# MAX31865.net
KiCad netlist of a schematic drawn in EAGLE
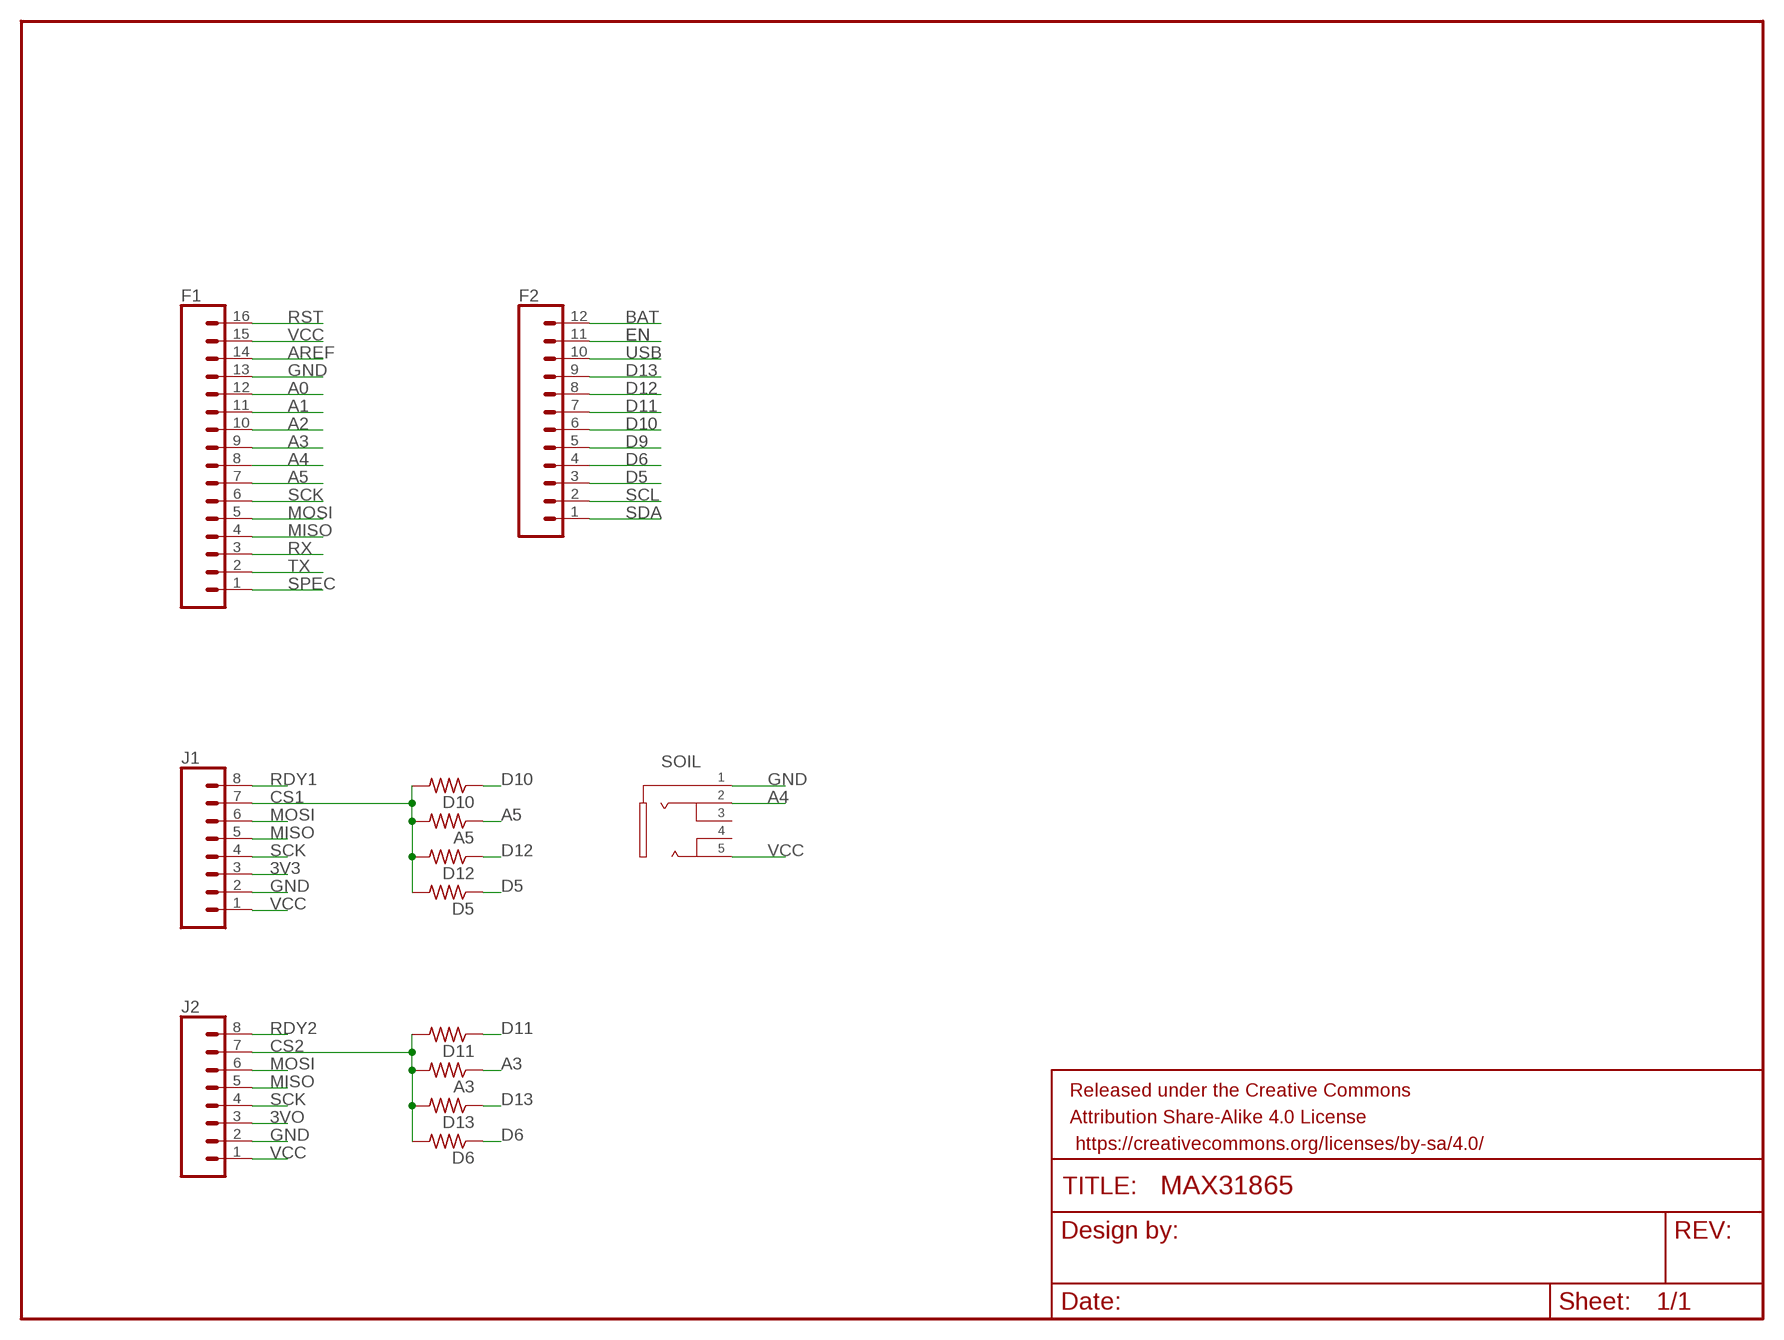
[diagram p0: schematic, sheet 1]

(export (version "E")
  (design (tool "Eeschema 10.0.6"))
  (components
    (comp (ref "A3")
      (value "R-US_R0603")
      (footprint "eagle-import:R0603")
      (libsource (lib "eagle-import") (part "R-US_R0603"))
    )
    (comp (ref "A5")
      (value "R-US_R0603")
      (footprint "eagle-import:R0603")
      (libsource (lib "eagle-import") (part "R-US_R0603"))
    )
    (comp (ref "D5")
      (value "R-US_R0603")
      (footprint "eagle-import:R0603")
      (libsource (lib "eagle-import") (part "R-US_R0603"))
    )
    (comp (ref "D6")
      (value "R-US_R0603")
      (footprint "eagle-import:R0603")
      (libsource (lib "eagle-import") (part "R-US_R0603"))
    )
    (comp (ref "D10")
      (value "R-US_R0603")
      (footprint "eagle-import:R0603")
      (libsource (lib "eagle-import") (part "R-US_R0603"))
    )
    (comp (ref "D11")
      (value "R-US_R0603")
      (footprint "eagle-import:R0603")
      (libsource (lib "eagle-import") (part "R-US_R0603"))
    )
    (comp (ref "D12")
      (value "R-US_R0603")
      (footprint "eagle-import:R0603")
      (libsource (lib "eagle-import") (part "R-US_R0603"))
    )
    (comp (ref "D13")
      (value "R-US_R0603")
      (footprint "eagle-import:R0603")
      (libsource (lib "eagle-import") (part "R-US_R0603"))
    )
    (comp (ref "F1")
      (value "CONN_16")
      (footprint "eagle-import:1X16")
      (libsource (lib "eagle-import") (part "CONN_16"))
    )
    (comp (ref "F2")
      (value "CONN_12")
      (footprint "eagle-import:1X12")
      (libsource (lib "eagle-import") (part "CONN_12"))
    )
    (comp (ref "FRAME1")
      (value "FRAME-LETTER")
      (footprint "eagle-import:CREATIVE_COMMONS")
      (libsource (lib "eagle-import") (part "FRAME-LETTER"))
    )
    (comp (ref "J1")
      (value "CONN_08\"")
      (footprint "eagle-import:1X08")
      (libsource (lib "eagle-import") (part "CONN_08{dblquote}"))
    )
    (comp (ref "J2")
      (value "CONN_08\"")
      (footprint "eagle-import:1X08")
      (libsource (lib "eagle-import") (part "CONN_08{dblquote}"))
    )
    (comp (ref "SOIL")
      (value "JW-PJ-307-5H")
      (footprint "eagle-import:JW-PJ-307-5H")
      (libsource (lib "eagle-import") (part "JW-PJ-307-5H"))
    )
  )
  (nets
    (net (code "1") (name "/3V3") (class "Default")
      (node (ref "J1") (pin "3") (pinfunction "3_3") (pintype "passive"))
    )
    (net (code "2") (name "/3VO") (class "Default")
      (node (ref "J2") (pin "3") (pinfunction "3_3") (pintype "passive"))
    )
    (net (code "3") (name "/A0") (class "Default")
      (node (ref "F1") (pin "12") (pinfunction "12_12") (pintype "passive"))
    )
    (net (code "4") (name "/A1") (class "Default")
      (node (ref "F1") (pin "11") (pinfunction "11_11") (pintype "passive"))
    )
    (net (code "5") (name "/A2") (class "Default")
      (node (ref "F1") (pin "10") (pinfunction "10_10") (pintype "passive"))
    )
    (net (code "6") (name "/A3") (class "Default")
      (node (ref "A3") (pin "1") (pinfunction "1_1") (pintype "passive"))
      (node (ref "F1") (pin "9") (pinfunction "9_9") (pintype "passive"))
    )
    (net (code "7") (name "/A4") (class "Default")
      (node (ref "F1") (pin "8") (pinfunction "8_8") (pintype "passive"))
      (node (ref "SOIL") (pin "2") (pinfunction "2_2") (pintype "passive"))
    )
    (net (code "8") (name "/A5") (class "Default")
      (node (ref "A5") (pin "1") (pinfunction "1_1") (pintype "passive"))
      (node (ref "F1") (pin "7") (pinfunction "7_7") (pintype "passive"))
    )
    (net (code "9") (name "/AREF") (class "Default")
      (node (ref "F1") (pin "14") (pinfunction "14_14") (pintype "passive"))
    )
    (net (code "10") (name "/BAT") (class "Default")
      (node (ref "F2") (pin "12") (pinfunction "12_12") (pintype "passive"))
    )
    (net (code "11") (name "/CS1") (class "Default")
      (node (ref "A5") (pin "2") (pinfunction "2_2") (pintype "passive"))
      (node (ref "D10") (pin "2") (pinfunction "2_2") (pintype "passive"))
      (node (ref "D12") (pin "2") (pinfunction "2_2") (pintype "passive"))
      (node (ref "D5") (pin "2") (pinfunction "2_2") (pintype "passive"))
      (node (ref "J1") (pin "7") (pinfunction "7_7") (pintype "passive"))
    )
    (net (code "12") (name "/CS2") (class "Default")
      (node (ref "A3") (pin "2") (pinfunction "2_2") (pintype "passive"))
      (node (ref "D11") (pin "2") (pinfunction "2_2") (pintype "passive"))
      (node (ref "D13") (pin "2") (pinfunction "2_2") (pintype "passive"))
      (node (ref "D6") (pin "2") (pinfunction "2_2") (pintype "passive"))
      (node (ref "J2") (pin "7") (pinfunction "7_7") (pintype "passive"))
    )
    (net (code "13") (name "/D5") (class "Default")
      (node (ref "D5") (pin "1") (pinfunction "1_1") (pintype "passive"))
      (node (ref "F2") (pin "3") (pinfunction "3_3") (pintype "passive"))
    )
    (net (code "14") (name "/D6") (class "Default")
      (node (ref "D6") (pin "1") (pinfunction "1_1") (pintype "passive"))
      (node (ref "F2") (pin "4") (pinfunction "4_4") (pintype "passive"))
    )
    (net (code "15") (name "/D9") (class "Default")
      (node (ref "F2") (pin "5") (pinfunction "5_5") (pintype "passive"))
    )
    (net (code "16") (name "/D10") (class "Default")
      (node (ref "D10") (pin "1") (pinfunction "1_1") (pintype "passive"))
      (node (ref "F2") (pin "6") (pinfunction "6_6") (pintype "passive"))
    )
    (net (code "17") (name "/D11") (class "Default")
      (node (ref "D11") (pin "1") (pinfunction "1_1") (pintype "passive"))
      (node (ref "F2") (pin "7") (pinfunction "7_7") (pintype "passive"))
    )
    (net (code "18") (name "/D12") (class "Default")
      (node (ref "D12") (pin "1") (pinfunction "1_1") (pintype "passive"))
      (node (ref "F2") (pin "8") (pinfunction "8_8") (pintype "passive"))
    )
    (net (code "19") (name "/D13") (class "Default")
      (node (ref "D13") (pin "1") (pinfunction "1_1") (pintype "passive"))
      (node (ref "F2") (pin "9") (pinfunction "9_9") (pintype "passive"))
    )
    (net (code "20") (name "/EN") (class "Default")
      (node (ref "F2") (pin "11") (pinfunction "11_11") (pintype "passive"))
    )
    (net (code "21") (name "/GND") (class "Default")
      (node (ref "F1") (pin "13") (pinfunction "13_13") (pintype "passive"))
      (node (ref "J1") (pin "2") (pinfunction "2_2") (pintype "passive"))
      (node (ref "J2") (pin "2") (pinfunction "2_2") (pintype "passive"))
      (node (ref "SOIL") (pin "1") (pinfunction "1_1") (pintype "passive"))
    )
    (net (code "22") (name "/MISO") (class "Default")
      (node (ref "F1") (pin "4") (pinfunction "4_4") (pintype "passive"))
      (node (ref "J1") (pin "5") (pinfunction "5_5") (pintype "passive"))
      (node (ref "J2") (pin "5") (pinfunction "5_5") (pintype "passive"))
    )
    (net (code "23") (name "/MOSI") (class "Default")
      (node (ref "F1") (pin "5") (pinfunction "5_5") (pintype "passive"))
      (node (ref "J1") (pin "6") (pinfunction "6_6") (pintype "passive"))
      (node (ref "J2") (pin "6") (pinfunction "6_6") (pintype "passive"))
    )
    (net (code "24") (name "/RDY1") (class "Default")
      (node (ref "J1") (pin "8") (pinfunction "8_8") (pintype "passive"))
    )
    (net (code "25") (name "/RDY2") (class "Default")
      (node (ref "J2") (pin "8") (pinfunction "8_8") (pintype "passive"))
    )
    (net (code "26") (name "/RST") (class "Default")
      (node (ref "F1") (pin "16") (pinfunction "16_16") (pintype "passive"))
    )
    (net (code "27") (name "/RX") (class "Default")
      (node (ref "F1") (pin "3") (pinfunction "3_3") (pintype "passive"))
    )
    (net (code "28") (name "/SCK") (class "Default")
      (node (ref "F1") (pin "6") (pinfunction "6_6") (pintype "passive"))
      (node (ref "J1") (pin "4") (pinfunction "4_4") (pintype "passive"))
      (node (ref "J2") (pin "4") (pinfunction "4_4") (pintype "passive"))
    )
    (net (code "29") (name "/SCL") (class "Default")
      (node (ref "F2") (pin "2") (pinfunction "2_2") (pintype "passive"))
    )
    (net (code "30") (name "/SDA") (class "Default")
      (node (ref "F2") (pin "1") (pinfunction "1_1") (pintype "passive"))
    )
    (net (code "31") (name "/SPEC") (class "Default")
      (node (ref "F1") (pin "1") (pinfunction "1_1") (pintype "passive"))
    )
    (net (code "32") (name "/TX") (class "Default")
      (node (ref "F1") (pin "2") (pinfunction "2_2") (pintype "passive"))
    )
    (net (code "33") (name "/USB") (class "Default")
      (node (ref "F2") (pin "10") (pinfunction "10_10") (pintype "passive"))
    )
    (net (code "34") (name "/VCC") (class "Default")
      (node (ref "F1") (pin "15") (pinfunction "15_15") (pintype "passive"))
      (node (ref "J1") (pin "1") (pinfunction "1_1") (pintype "passive"))
      (node (ref "J2") (pin "1") (pinfunction "1_1") (pintype "passive"))
      (node (ref "SOIL") (pin "5") (pinfunction "5_5") (pintype "passive"))
    )
    (net (code "35") (name "unconnected-(SOIL-Pad3)") (class "Default")
      (node (ref "SOIL") (pin "3") (pinfunction "3_3") (pintype "passive"))
    )
    (net (code "36") (name "unconnected-(SOIL-Pad4)") (class "Default")
      (node (ref "SOIL") (pin "4") (pinfunction "4_4") (pintype "passive"))
    )
  )
)
